# drill_charger.net
KiCad netlist of a schematic drawn in EAGLE
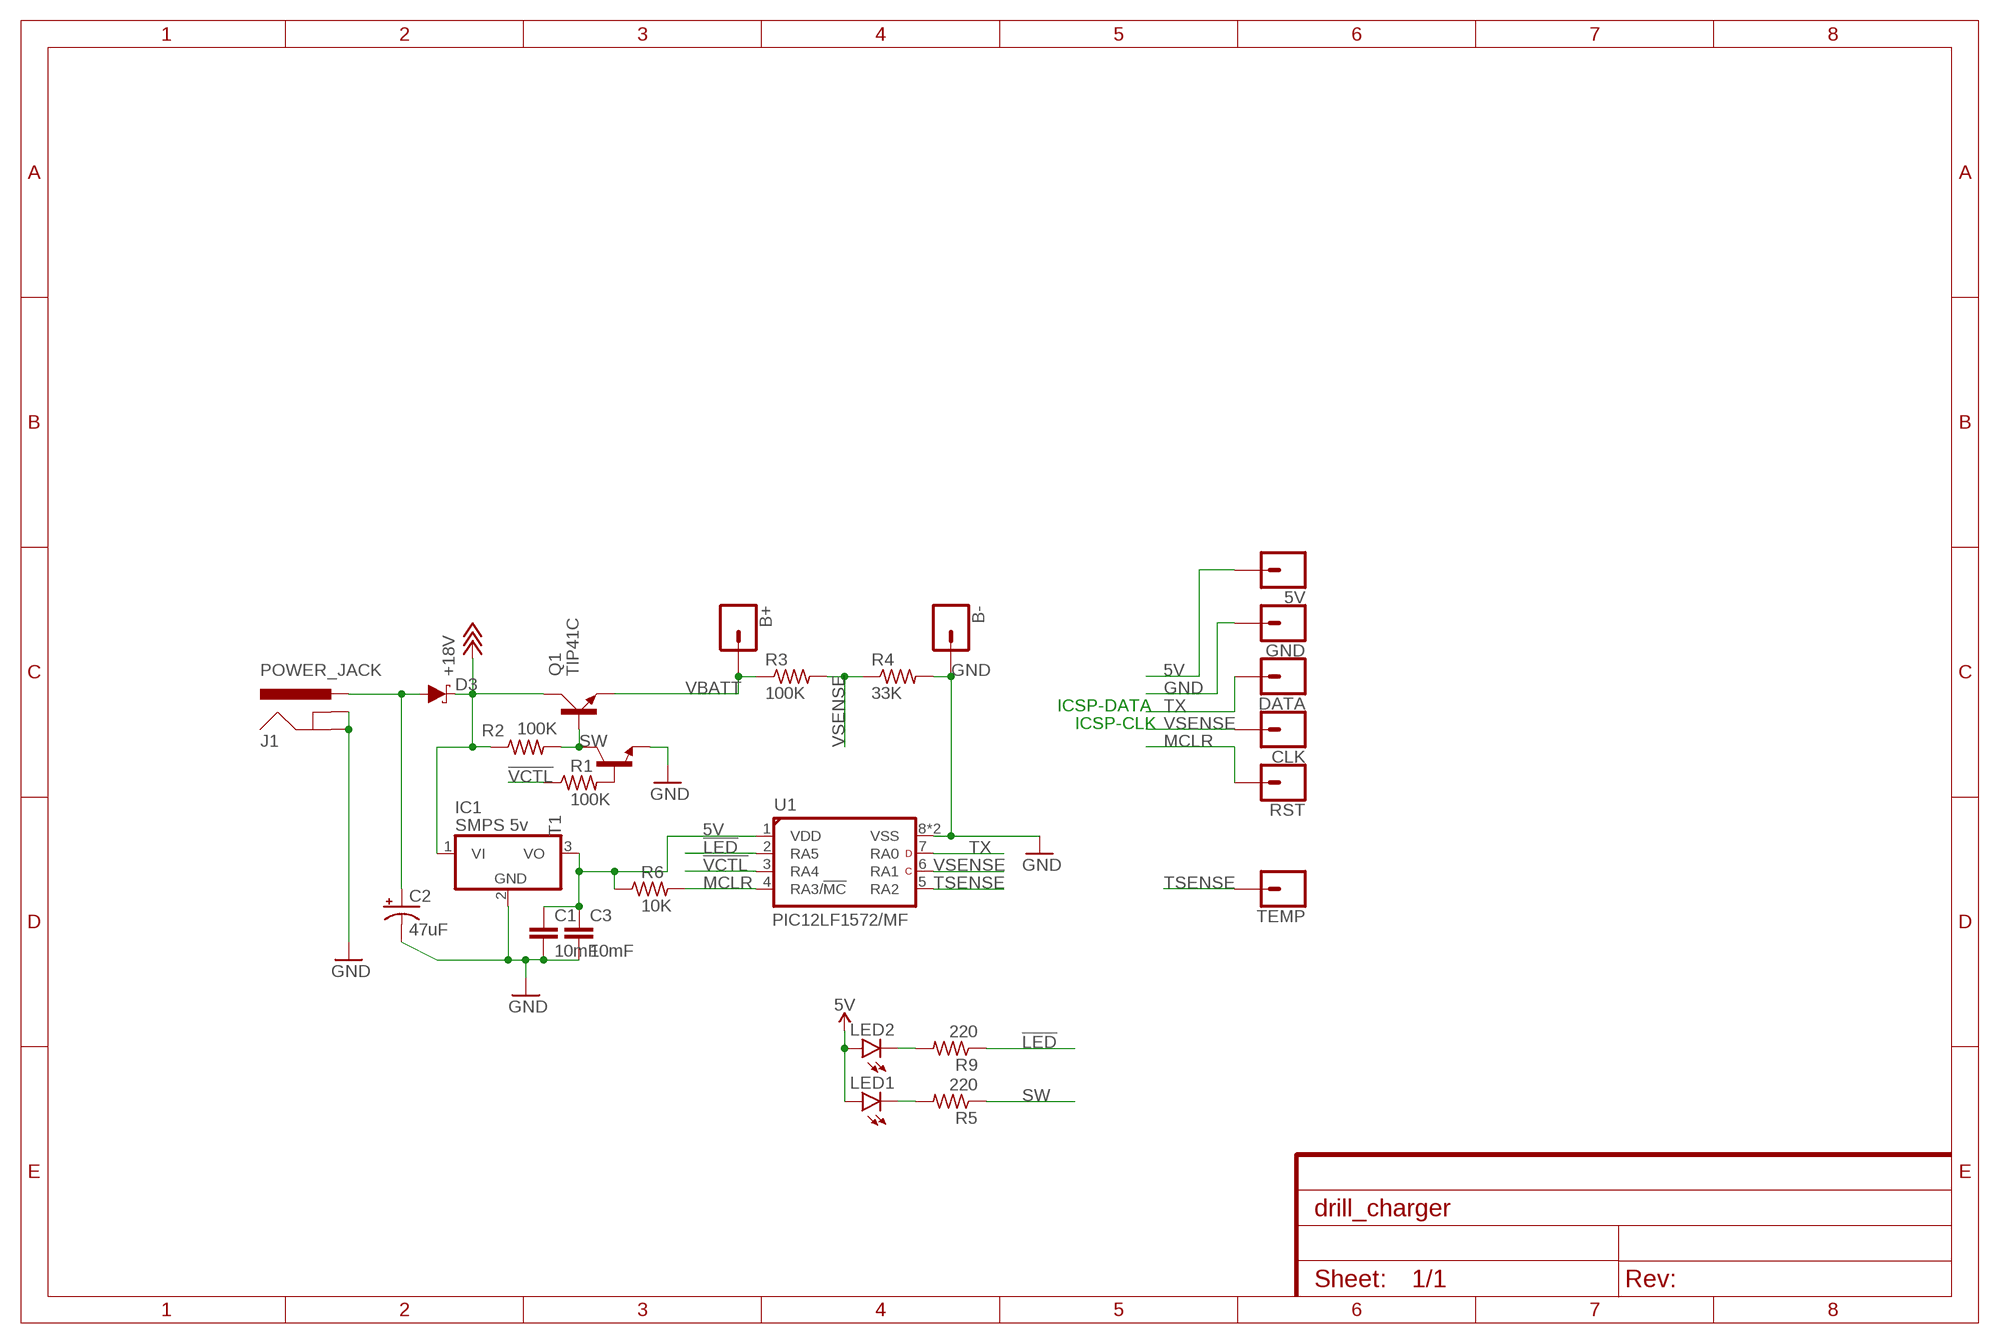
[diagram p0: schematic, sheet 1]

(export (version "E")
  (design (tool "Eeschema 10.0.6"))
  (components
    (comp (ref "5V")
      (value "CONN_01")
      (footprint "eagle-import:1X01")
      (libsource (lib "eagle-import") (part "CONN_01"))
    )
    (comp (ref "B+")
      (value "CONN_01")
      (footprint "eagle-import:1X01")
      (libsource (lib "eagle-import") (part "CONN_01"))
    )
    (comp (ref "B-")
      (value "CONN_01")
      (footprint "eagle-import:1X01")
      (libsource (lib "eagle-import") (part "CONN_01"))
    )
    (comp (ref "C1")
      (value "10mF")
      (footprint "eagle-import:C0805")
      (libsource (lib "eagle-import") (part "C-EUC0805"))
    )
    (comp (ref "C2")
      (value "47uF")
      (footprint "eagle-import:CPOL-RADIAL-2.5MM-6.5MM")
      (libsource (lib "eagle-import") (part "100UF-POLAR-RADIAL-2.5MM-25V-20%"))
    )
    (comp (ref "C3")
      (value "10mF")
      (footprint "eagle-import:C0805")
      (libsource (lib "eagle-import") (part "C-EUC0805"))
    )
    (comp (ref "CLK")
      (value "CONN_01")
      (footprint "eagle-import:1X01")
      (libsource (lib "eagle-import") (part "CONN_01"))
    )
    (comp (ref "D3")
      (value "1A/40V/500mV")
      (footprint "eagle-import:SMA-DIODE")
      (libsource (lib "eagle-import") (part "DIODE-SCHOTTKY-SS14"))
    )
    (comp (ref "DATA")
      (value "CONN_01")
      (footprint "eagle-import:1X01")
      (libsource (lib "eagle-import") (part "CONN_01"))
    )
    (comp (ref "GND")
      (value "CONN_01")
      (footprint "eagle-import:1X01")
      (libsource (lib "eagle-import") (part "CONN_01"))
    )
    (comp (ref "IC1")
      (value "SMPS 5v")
      (footprint "eagle-import:TO220V")
      (libsource (lib "eagle-import") (part "78TV05"))
    )
    (comp (ref "J1")
      (value "POWER_JACK")
      (footprint "eagle-import:POWER_JACK_PTH")
      (libsource (lib "eagle-import") (part "POWER_JACK"))
    )
    (comp (ref "LED1")
      (value "LED3MM")
      (footprint "eagle-import:LED3MM")
      (libsource (lib "eagle-import") (part "LED3MM"))
    )
    (comp (ref "LED2")
      (value "LED3MM")
      (footprint "eagle-import:LED3MM")
      (libsource (lib "eagle-import") (part "LED3MM"))
    )
    (comp (ref "Q1")
      (value "TIP41C")
      (footprint "eagle-import:TO220AV")
      (libsource (lib "eagle-import") (part "TIP41C"))
    )
    (comp (ref "R1")
      (value "100K")
      (footprint "eagle-import:R0805")
      (libsource (lib "eagle-import") (part "R-US_R0805"))
    )
    (comp (ref "R2")
      (value "100K")
      (footprint "eagle-import:R0805")
      (libsource (lib "eagle-import") (part "R-US_R0805"))
    )
    (comp (ref "R3")
      (value "100K")
      (footprint "eagle-import:R1206")
      (libsource (lib "eagle-import") (part "R-US_R1206"))
    )
    (comp (ref "R4")
      (value "33K")
      (footprint "eagle-import:R1206")
      (libsource (lib "eagle-import") (part "R-US_R1206"))
    )
    (comp (ref "R5")
      (value "220")
      (footprint "eagle-import:R0805")
      (libsource (lib "eagle-import") (part "R-US_R0805"))
    )
    (comp (ref "R6")
      (value "10K")
      (footprint "eagle-import:R0805")
      (libsource (lib "eagle-import") (part "R-US_R0805"))
    )
    (comp (ref "R9")
      (value "220")
      (footprint "eagle-import:R0805")
      (libsource (lib "eagle-import") (part "R-US_R0805"))
    )
    (comp (ref "RST")
      (value "CONN_01")
      (footprint "eagle-import:1X01")
      (libsource (lib "eagle-import") (part "CONN_01"))
    )
    (comp (ref "T1")
      (value "MMBT3904LT1-NPN-SOT23-BEC")
      (footprint "eagle-import:SOT23-BEC")
      (libsource (lib "eagle-import") (part "-NPN-SOT23-BECMMBT3904LT1"))
    )
    (comp (ref "TEMP")
      (value "CONN_01")
      (footprint "eagle-import:1X01")
      (libsource (lib "eagle-import") (part "CONN_01"))
    )
    (comp (ref "U1")
      (value "PIC12LF1572/MF")
      (footprint "eagle-import:DFN8-MF")
      (libsource (lib "eagle-import") (part "PIC12F1572/MFL"))
    )
  )
  (nets
    (net (code "1") (name "+18V") (class "Default")
      (node (ref "D3") (pin "C") (pinfunction "C_C") (pintype "passive"))
      (node (ref "IC1") (pin "1") (pinfunction "VI_1") (pintype "input"))
      (node (ref "Q1") (pin "C") (pinfunction "C_C") (pintype "passive"))
      (node (ref "R2") (pin "1") (pinfunction "1_1") (pintype "passive"))
    )
    (net (code "2") (name "/MCLR") (class "Default")
      (node (ref "R6") (pin "2") (pinfunction "2_2") (pintype "passive"))
      (node (ref "RST") (pin "1") (pinfunction "1_1") (pintype "passive"))
      (node (ref "U1") (pin "4") (pinfunction "RA3/~{MC}_4") (pintype "bidirectional"))
    )
    (net (code "3") (name "/SW") (class "Default")
      (node (ref "Q1") (pin "B") (pinfunction "B_B") (pintype "passive"))
      (node (ref "R2") (pin "2") (pinfunction "2_2") (pintype "passive"))
      (node (ref "R5") (pin "1") (pinfunction "1_1") (pintype "passive"))
      (node (ref "T1") (pin "C") (pinfunction "C_C") (pintype "passive"))
    )
    (net (code "4") (name "/TSENSE") (class "Default")
      (node (ref "TEMP") (pin "1") (pinfunction "1_1") (pintype "passive"))
      (node (ref "U1") (pin "5") (pinfunction "RA2_5") (pintype "bidirectional"))
    )
    (net (code "5") (name "/TX") (class "Default")
      (node (ref "DATA") (pin "1") (pinfunction "1_1") (pintype "passive"))
      (node (ref "U1") (pin "7") (pinfunction "RA0_7") (pintype "bidirectional"))
    )
    (net (code "6") (name "/VBATT") (class "Default")
      (node (ref "B+") (pin "1") (pinfunction "1_1") (pintype "passive"))
      (node (ref "Q1") (pin "E") (pinfunction "E_E") (pintype "passive"))
      (node (ref "R3") (pin "1") (pinfunction "1_1") (pintype "passive"))
    )
    (net (code "7") (name "/VSENSE") (class "Default")
      (node (ref "CLK") (pin "1") (pinfunction "1_1") (pintype "passive"))
      (node (ref "R3") (pin "2") (pinfunction "2_2") (pintype "passive"))
      (node (ref "R4") (pin "1") (pinfunction "1_1") (pintype "passive"))
      (node (ref "U1") (pin "6") (pinfunction "RA1_6") (pintype "bidirectional"))
    )
    (net (code "8") (name "/~{LED}") (class "Default")
      (node (ref "R9") (pin "1") (pinfunction "1_1") (pintype "passive"))
      (node (ref "U1") (pin "2") (pinfunction "RA5_2") (pintype "bidirectional"))
    )
    (net (code "9") (name "/~{VCTL}") (class "Default")
      (node (ref "R1") (pin "1") (pinfunction "1_1") (pintype "passive"))
      (node (ref "U1") (pin "3") (pinfunction "RA4_3") (pintype "bidirectional"))
    )
    (net (code "10") (name "5V") (class "Default")
      (node (ref "5V") (pin "1") (pinfunction "1_1") (pintype "passive"))
      (node (ref "C1") (pin "1") (pinfunction "1_1") (pintype "passive"))
      (node (ref "C3") (pin "1") (pinfunction "1_1") (pintype "passive"))
      (node (ref "IC1") (pin "3") (pinfunction "VO_3") (pintype "passive"))
      (node (ref "LED1") (pin "A") (pinfunction "A_A") (pintype "passive"))
      (node (ref "LED2") (pin "A") (pinfunction "A_A") (pintype "passive"))
      (node (ref "R6") (pin "1") (pinfunction "1_1") (pintype "passive"))
      (node (ref "U1") (pin "1") (pinfunction "VDD_1") (pintype "passive"))
    )
    (net (code "11") (name "GND") (class "Default")
      (node (ref "B-") (pin "1") (pinfunction "1_1") (pintype "passive"))
      (node (ref "C1") (pin "2") (pinfunction "2_2") (pintype "passive"))
      (node (ref "C2") (pin "2") (pinfunction "-_2") (pintype "passive"))
      (node (ref "C3") (pin "2") (pinfunction "2_2") (pintype "passive"))
      (node (ref "GND") (pin "1") (pinfunction "1_1") (pintype "passive"))
      (node (ref "IC1") (pin "2") (pinfunction "GND_2") (pintype "passive"))
      (node (ref "J1") (pin "GND") (pinfunction "GND_GND") (pintype "bidirectional"))
      (node (ref "J1") (pin "GNDBREAK") (pinfunction "GNDBREAK_GNDBREAK") (pintype "bidirectional"))
      (node (ref "R4") (pin "2") (pinfunction "2_2") (pintype "passive"))
      (node (ref "T1") (pin "E") (pinfunction "E_E") (pintype "passive"))
      (node (ref "U1") (pin "8") (pinfunction "VSS_8") (pintype "passive"))
      (node (ref "U1") (pin "EP") (pinfunction "VSS_EP") (pintype "passive"))
    )
    (net (code "12") (name "Net-(C2-+)") (class "Default")
      (node (ref "C2") (pin "1") (pinfunction "+_1") (pintype "passive"))
      (node (ref "D3") (pin "A") (pinfunction "A_A") (pintype "passive"))
      (node (ref "J1") (pin "PWR") (pinfunction "PWR_PWR") (pintype "bidirectional"))
    )
    (net (code "13") (name "Net-(LED1-C)") (class "Default")
      (node (ref "LED1") (pin "K") (pinfunction "C_K") (pintype "passive"))
      (node (ref "R5") (pin "2") (pinfunction "2_2") (pintype "passive"))
    )
    (net (code "14") (name "Net-(LED2-C)") (class "Default")
      (node (ref "LED2") (pin "K") (pinfunction "C_K") (pintype "passive"))
      (node (ref "R9") (pin "2") (pinfunction "2_2") (pintype "passive"))
    )
    (net (code "15") (name "Net-(R1-Pad2)") (class "Default")
      (node (ref "R1") (pin "2") (pinfunction "2_2") (pintype "passive"))
      (node (ref "T1") (pin "B") (pinfunction "B_B") (pintype "passive"))
    )
  )
)
